# Power.net
KiCad netlist of a schematic drawn in Altium Designer
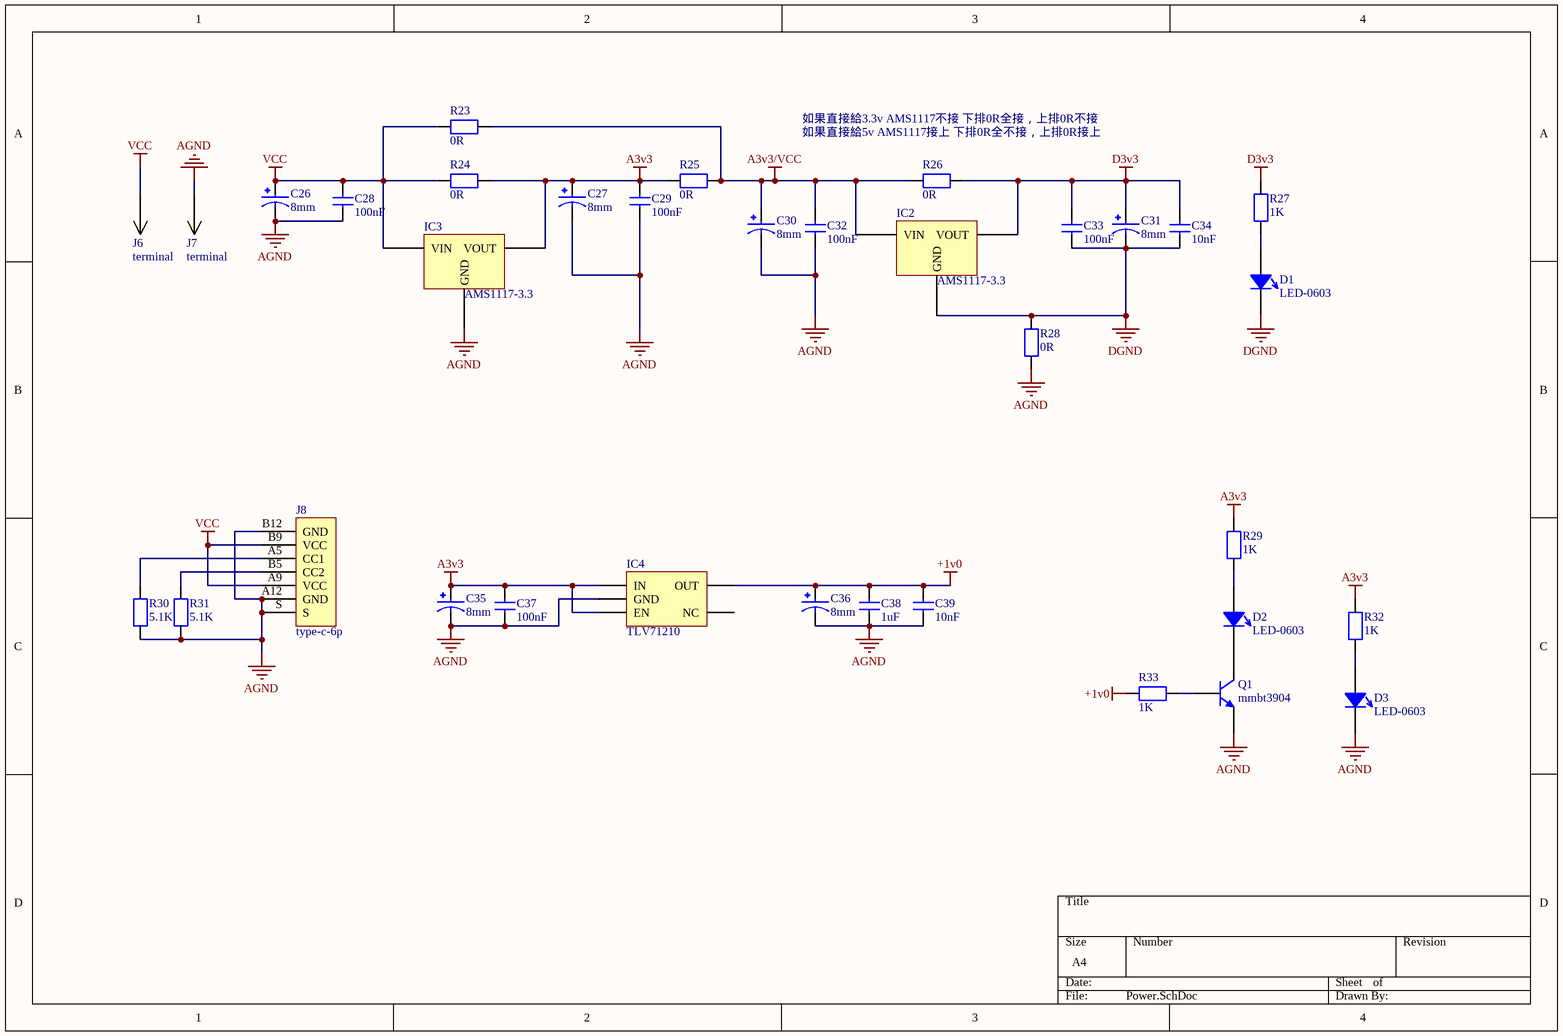
[diagram p0: Power.SchDoc]

(export (version "E")
  (design (tool "Eeschema 10.0.6"))
  (components
    (comp (ref "C26")
      (value "8mm")
      (footprint "CAP_dual")
      (description "8mm cap")
      (libsource (lib "Switch_Schlib") (part "dip-cap"))
    )
    (comp (ref "C27")
      (value "8mm")
      (footprint "CAP_dual")
      (description "8mm cap")
      (libsource (lib "Switch_Schlib") (part "dip-cap"))
    )
    (comp (ref "C28")
      (value "100nF")
      (footprint "C-0603")
      (description "C-0603")
      (libsource (lib "Switch_Schlib") (part "C-0603"))
    )
    (comp (ref "C29")
      (value "100nF")
      (footprint "C-0603")
      (description "C-0603")
      (libsource (lib "Switch_Schlib") (part "C-0603"))
    )
    (comp (ref "C30")
      (value "8mm")
      (footprint "CAP_dual")
      (description "8mm cap")
      (libsource (lib "Switch_Schlib") (part "dip-cap"))
    )
    (comp (ref "C31")
      (value "8mm")
      (footprint "CAP_dual")
      (description "8mm cap")
      (libsource (lib "Switch_Schlib") (part "dip-cap"))
    )
    (comp (ref "C32")
      (value "100nF")
      (footprint "C-0603")
      (description "C-0603")
      (libsource (lib "Switch_Schlib") (part "C-0603"))
    )
    (comp (ref "C33")
      (value "100nF")
      (footprint "C-0603")
      (description "C-0603")
      (libsource (lib "Switch_Schlib") (part "C-0603"))
    )
    (comp (ref "C34")
      (value "10nF")
      (footprint "C-0603")
      (description "C-0603")
      (libsource (lib "Switch_Schlib") (part "C-0603"))
    )
    (comp (ref "C35")
      (value "8mm")
      (footprint "CAP_dual")
      (description "8mm cap")
      (libsource (lib "Switch_Schlib") (part "dip-cap"))
    )
    (comp (ref "C36")
      (value "8mm")
      (footprint "CAP_dual")
      (description "8mm cap")
      (libsource (lib "Switch_Schlib") (part "dip-cap"))
    )
    (comp (ref "C37")
      (value "100nF")
      (footprint "C-0603")
      (description "C-0603")
      (libsource (lib "Switch_Schlib") (part "C-0603"))
    )
    (comp (ref "C38")
      (value "1uF")
      (footprint "C-0603")
      (description "C-0603")
      (libsource (lib "Switch_Schlib") (part "C-0603"))
    )
    (comp (ref "C39")
      (value "10nF")
      (footprint "C-0603")
      (description "C-0603")
      (libsource (lib "Switch_Schlib") (part "C-0603"))
    )
    (comp (ref "D1")
      (value "LED-0603")
      (footprint "LED-0603")
      (libsource (lib "Switch_Schlib") (part "LED-0603"))
    )
    (comp (ref "D2")
      (value "LED-0603")
      (footprint "LED-0603")
      (libsource (lib "Switch_Schlib") (part "LED-0603"))
    )
    (comp (ref "D3")
      (value "LED-0603")
      (footprint "LED-0603")
      (libsource (lib "Switch_Schlib") (part "LED-0603"))
    )
    (comp (ref "IC2")
      (value "AMS1117-3.3")
      (footprint "SOT-223")
      (libsource (lib "Switch_Schlib") (part "AMS1117-3.3"))
    )
    (comp (ref "IC3")
      (value "AMS1117-3.3")
      (footprint "SOT-223")
      (libsource (lib "Switch_Schlib") (part "AMS1117-3.3"))
    )
    (comp (ref "IC4")
      (value "TLV71210")
      (footprint "SOT95P245X110-5L")
      (description "1V LDO TLV71210DBVR / AP7335-10WG-7")
      (libsource (lib "Switch_Schlib") (part "TLV71210"))
    )
    (comp (ref "J6")
      (value "terminal")
      (footprint "Terminal-6.3mm")
      (description "6.3mm-terminal")
      (libsource (lib "Switch_Schlib") (part "6.3mm-terminal"))
    )
    (comp (ref "J7")
      (value "terminal")
      (footprint "Terminal-6.3mm")
      (description "6.3mm-terminal")
      (libsource (lib "Switch_Schlib") (part "6.3mm-terminal"))
    )
    (comp (ref "J8")
      (value "type-c-6p")
      (footprint "type-c_6p")
      (description "C668623")
      (libsource (lib "Switch_Schlib") (part "type-c-6p"))
    )
    (comp (ref "Q1")
      (value "mmbt3904")
      (footprint "SOT23-L")
      (description "NPN")
      (libsource (lib "Switch_Schlib") (part "NPN"))
    )
    (comp (ref "R23")
      (value "0R")
      (footprint "RESMELF3515L")
      (description "Bypass")
      (libsource (lib "Switch_Schlib") (part "CSR-0204"))
    )
    (comp (ref "R24")
      (value "0R")
      (footprint "RESMELF3515L")
      (description "Bypsaa")
      (libsource (lib "Switch_Schlib") (part "CSR-0204"))
    )
    (comp (ref "R25")
      (value "0R")
      (footprint "RESMELF3515L")
      (description "Bypass")
      (libsource (lib "Switch_Schlib") (part "CSR-0204"))
    )
    (comp (ref "R26")
      (value "0R")
      (footprint "RESMELF3515L")
      (description "Bypass")
      (libsource (lib "Switch_Schlib") (part "CSR-0204"))
    )
    (comp (ref "R27")
      (value "1K")
      (footprint "RESMELF3515L")
      (description "CSR-0204")
      (libsource (lib "Switch_Schlib") (part "CSR-0204"))
    )
    (comp (ref "R28")
      (value "0R")
      (footprint "RESMELF3515L")
      (description "Bypass")
      (libsource (lib "Switch_Schlib") (part "CSR-0204"))
    )
    (comp (ref "R29")
      (value "1K")
      (footprint "RESMELF3515L")
      (description "CSR-0204")
      (libsource (lib "Switch_Schlib") (part "CSR-0204"))
    )
    (comp (ref "R30")
      (value "5.1K")
      (footprint "R-0603")
      (description "R-0603")
      (libsource (lib "Switch_Schlib") (part "R-0603"))
    )
    (comp (ref "R31")
      (value "5.1K")
      (footprint "R-0603")
      (description "R-0603")
      (libsource (lib "Switch_Schlib") (part "R-0603"))
    )
    (comp (ref "R32")
      (value "1K")
      (footprint "RESMELF3515L")
      (description "CSR-0204")
      (libsource (lib "Switch_Schlib") (part "CSR-0204"))
    )
    (comp (ref "R33")
      (value "1K")
      (footprint "RESMELF3515L")
      (description "CSR-0204")
      (libsource (lib "Switch_Schlib") (part "CSR-0204"))
    )
  )
  (nets
    (net (code "1") (name "+1v0") (class "Default")
      (node (ref "C36") (pin "1") (pinfunction "1_1") (pintype "passive"))
      (node (ref "C38") (pin "2") (pintype "passive"))
      (node (ref "C39") (pin "2") (pintype "passive"))
      (node (ref "IC4") (pin "5") (pinfunction "OUT_5") (pintype "passive"))
      (node (ref "R33") (pin "2") (pintype "passive"))
    )
    (net (code "2") (name "A3v3") (class "Default")
      (node (ref "C27") (pin "1") (pinfunction "1_1") (pintype "passive"))
      (node (ref "C29") (pin "2") (pintype "passive"))
      (node (ref "C35") (pin "1") (pinfunction "1_1") (pintype "passive"))
      (node (ref "C37") (pin "2") (pintype "passive"))
      (node (ref "IC3") (pin "2") (pinfunction "VOUT_2") (pintype "passive"))
      (node (ref "IC4") (pin "1") (pinfunction "IN_1") (pintype "passive"))
      (node (ref "IC4") (pin "3") (pinfunction "EN_3") (pintype "passive"))
      (node (ref "R24") (pin "2") (pintype "passive"))
      (node (ref "R25") (pin "1") (pintype "passive"))
      (node (ref "R29") (pin "2") (pintype "passive"))
      (node (ref "R32") (pin "2") (pintype "passive"))
    )
    (net (code "3") (name "A3v3{slash}VCC") (class "Default")
      (node (ref "C30") (pin "1") (pinfunction "1_1") (pintype "passive"))
      (node (ref "C32") (pin "2") (pintype "passive"))
      (node (ref "IC2") (pin "3") (pinfunction "VIN_3") (pintype "passive"))
      (node (ref "R23") (pin "2") (pintype "passive"))
      (node (ref "R25") (pin "2") (pintype "passive"))
      (node (ref "R26") (pin "1") (pintype "passive"))
    )
    (net (code "4") (name "AGND") (class "Default")
      (node (ref "C26") (pin "2") (pinfunction "2_2") (pintype "passive"))
      (node (ref "C27") (pin "2") (pinfunction "2_2") (pintype "passive"))
      (node (ref "C28") (pin "1") (pintype "passive"))
      (node (ref "C29") (pin "1") (pintype "passive"))
      (node (ref "C30") (pin "2") (pinfunction "2_2") (pintype "passive"))
      (node (ref "C32") (pin "1") (pintype "passive"))
      (node (ref "C35") (pin "2") (pinfunction "2_2") (pintype "passive"))
      (node (ref "C36") (pin "2") (pinfunction "2_2") (pintype "passive"))
      (node (ref "C37") (pin "1") (pintype "passive"))
      (node (ref "C38") (pin "1") (pintype "passive"))
      (node (ref "C39") (pin "1") (pintype "passive"))
      (node (ref "D3") (pin "2") (pinfunction "2_2") (pintype "passive"))
      (node (ref "IC3") (pin "1") (pinfunction "GND_1") (pintype "passive"))
      (node (ref "IC4") (pin "2") (pinfunction "GND_2") (pintype "passive"))
      (node (ref "J7") (pin "1") (pinfunction "1_1") (pintype "passive"))
      (node (ref "J8") (pin "A12") (pinfunction "GND_A12") (pintype "passive"))
      (node (ref "J8") (pin "B12") (pinfunction "GND_B12") (pintype "passive"))
      (node (ref "J8") (pin "S") (pinfunction "S_S") (pintype "passive"))
      (node (ref "Q1") (pin "2") (pinfunction "E_2") (pintype "passive"))
      (node (ref "R28") (pin "1") (pintype "passive"))
      (node (ref "R30") (pin "2") (pintype "passive"))
      (node (ref "R31") (pin "2") (pintype "passive"))
    )
    (net (code "5") (name "D3v3") (class "Default")
      (node (ref "C31") (pin "1") (pinfunction "1_1") (pintype "passive"))
      (node (ref "C33") (pin "2") (pintype "passive"))
      (node (ref "C34") (pin "2") (pintype "passive"))
      (node (ref "IC2") (pin "2") (pinfunction "VOUT_2") (pintype "passive"))
      (node (ref "R26") (pin "2") (pintype "passive"))
      (node (ref "R27") (pin "2") (pintype "passive"))
    )
    (net (code "6") (name "DGND") (class "Default")
      (node (ref "C31") (pin "2") (pinfunction "2_2") (pintype "passive"))
      (node (ref "C33") (pin "1") (pintype "passive"))
      (node (ref "C34") (pin "1") (pintype "passive"))
      (node (ref "D1") (pin "2") (pinfunction "2_2") (pintype "passive"))
      (node (ref "IC2") (pin "1") (pinfunction "GND_1") (pintype "passive"))
      (node (ref "R28") (pin "2") (pintype "passive"))
    )
    (net (code "7") (name "Net-(D1-Pad1)") (class "Default")
      (node (ref "D1") (pin "1") (pinfunction "1_1") (pintype "passive"))
      (node (ref "R27") (pin "1") (pintype "passive"))
    )
    (net (code "8") (name "Net-(D2-Pad1)") (class "Default")
      (node (ref "D2") (pin "1") (pinfunction "1_1") (pintype "passive"))
      (node (ref "R29") (pin "1") (pintype "passive"))
    )
    (net (code "9") (name "Net-(D3-Pad1)") (class "Default")
      (node (ref "D3") (pin "1") (pinfunction "1_1") (pintype "passive"))
      (node (ref "R32") (pin "1") (pintype "passive"))
    )
    (net (code "10") (name "Net-(J8-CC1)") (class "Default")
      (node (ref "J8") (pin "A5") (pinfunction "CC1_A5") (pintype "passive"))
      (node (ref "R30") (pin "1") (pintype "passive"))
    )
    (net (code "11") (name "Net-(J8-CC2)") (class "Default")
      (node (ref "J8") (pin "B5") (pinfunction "CC2_B5") (pintype "passive"))
      (node (ref "R31") (pin "1") (pintype "passive"))
    )
    (net (code "12") (name "Net-(Q1-B)") (class "Default")
      (node (ref "Q1") (pin "1") (pinfunction "B_1") (pintype "passive"))
      (node (ref "R33") (pin "1") (pintype "passive"))
    )
    (net (code "13") (name "Net-(Q1-C)") (class "Default")
      (node (ref "D2") (pin "2") (pinfunction "2_2") (pintype "passive"))
      (node (ref "Q1") (pin "3") (pinfunction "C_3") (pintype "passive"))
    )
    (net (code "14") (name "VCC") (class "Default")
      (node (ref "C26") (pin "1") (pinfunction "1_1") (pintype "passive"))
      (node (ref "C28") (pin "2") (pintype "passive"))
      (node (ref "IC3") (pin "3") (pinfunction "VIN_3") (pintype "passive"))
      (node (ref "J6") (pin "1") (pinfunction "1_1") (pintype "passive"))
      (node (ref "J8") (pin "A9") (pinfunction "VCC_A9") (pintype "passive"))
      (node (ref "J8") (pin "B9") (pinfunction "VCC_B9") (pintype "passive"))
      (node (ref "R23") (pin "1") (pintype "passive"))
      (node (ref "R24") (pin "1") (pintype "passive"))
    )
    (net (code "15") (name "unconnected-(IC4-NC-Pad4)") (class "Default")
      (node (ref "IC4") (pin "4") (pinfunction "NC_4") (pintype "passive"))
    )
  )
)
